# Mainboard.net
KiCad netlist of a schematic drawn in EAGLE
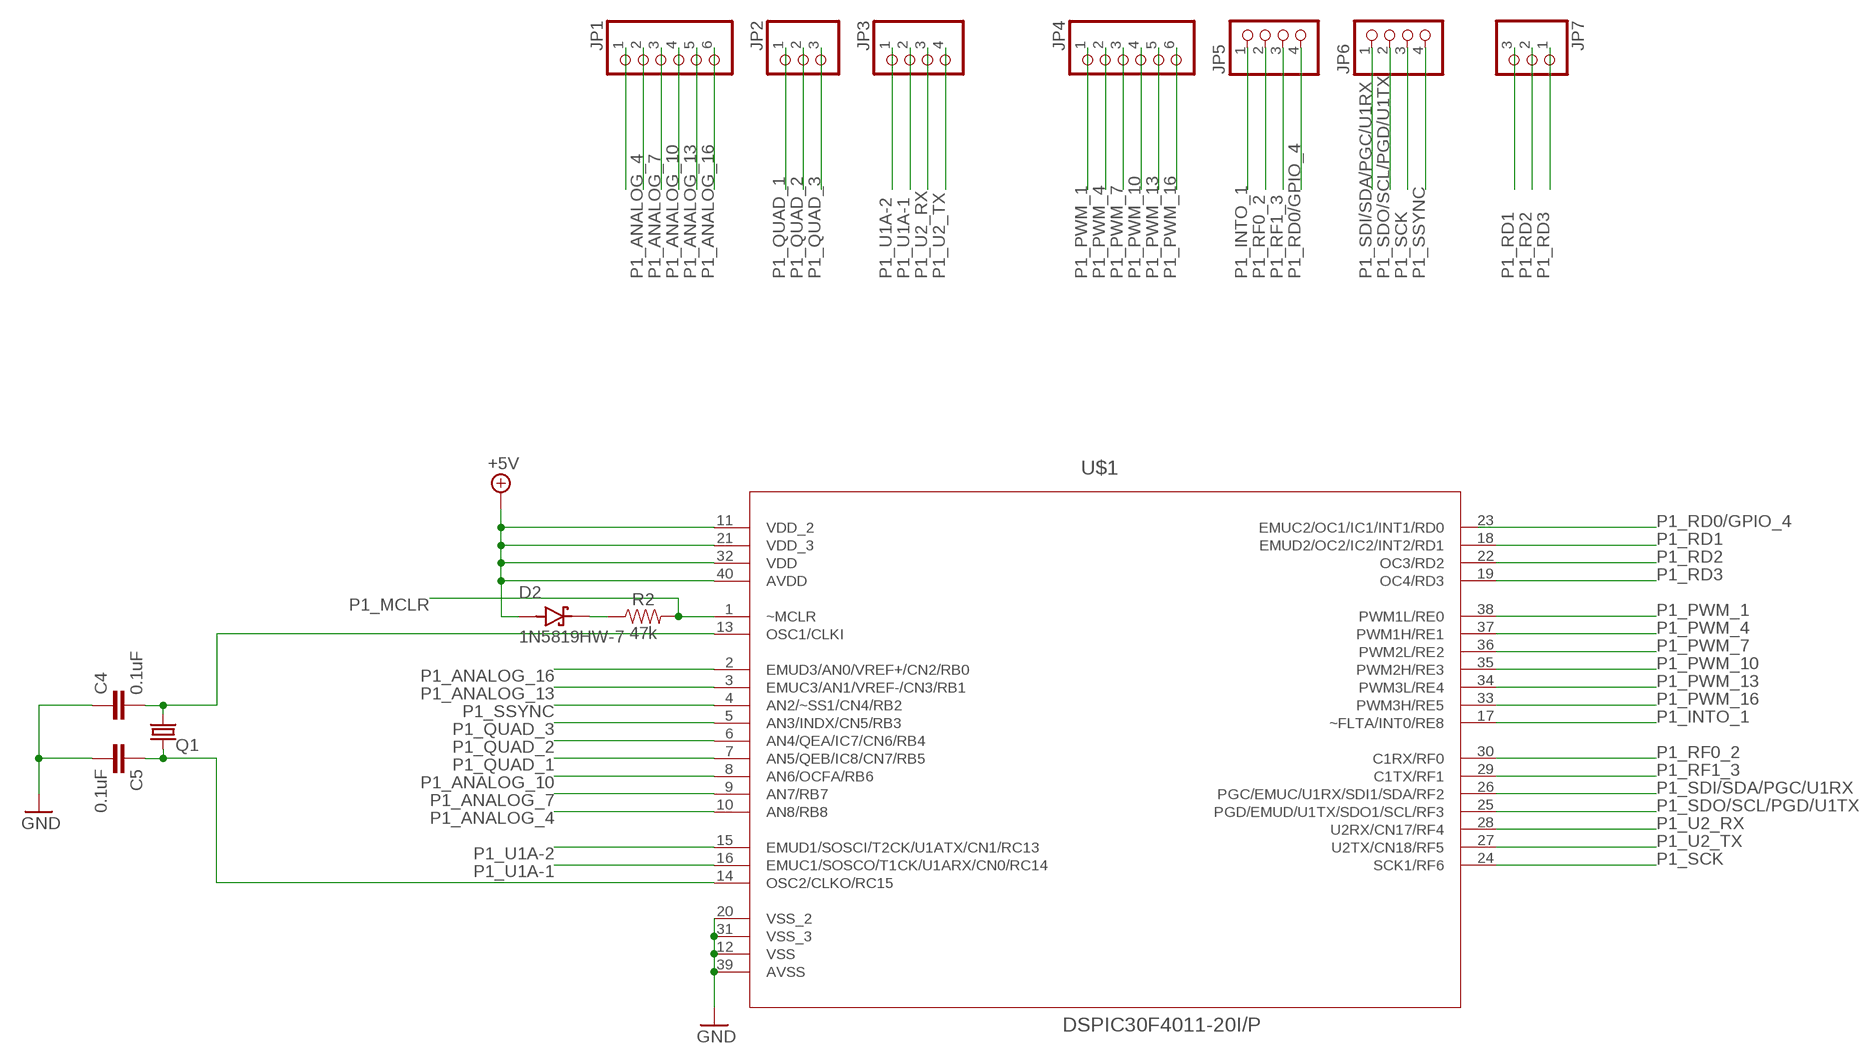
[diagram p0: schematic, sheet 2]
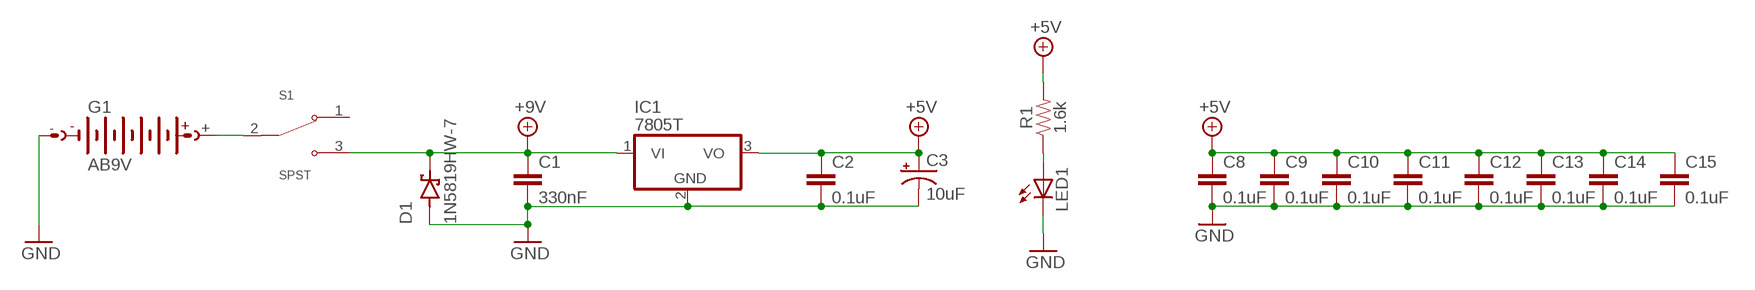
[diagram p1: schematic, sheet 3]
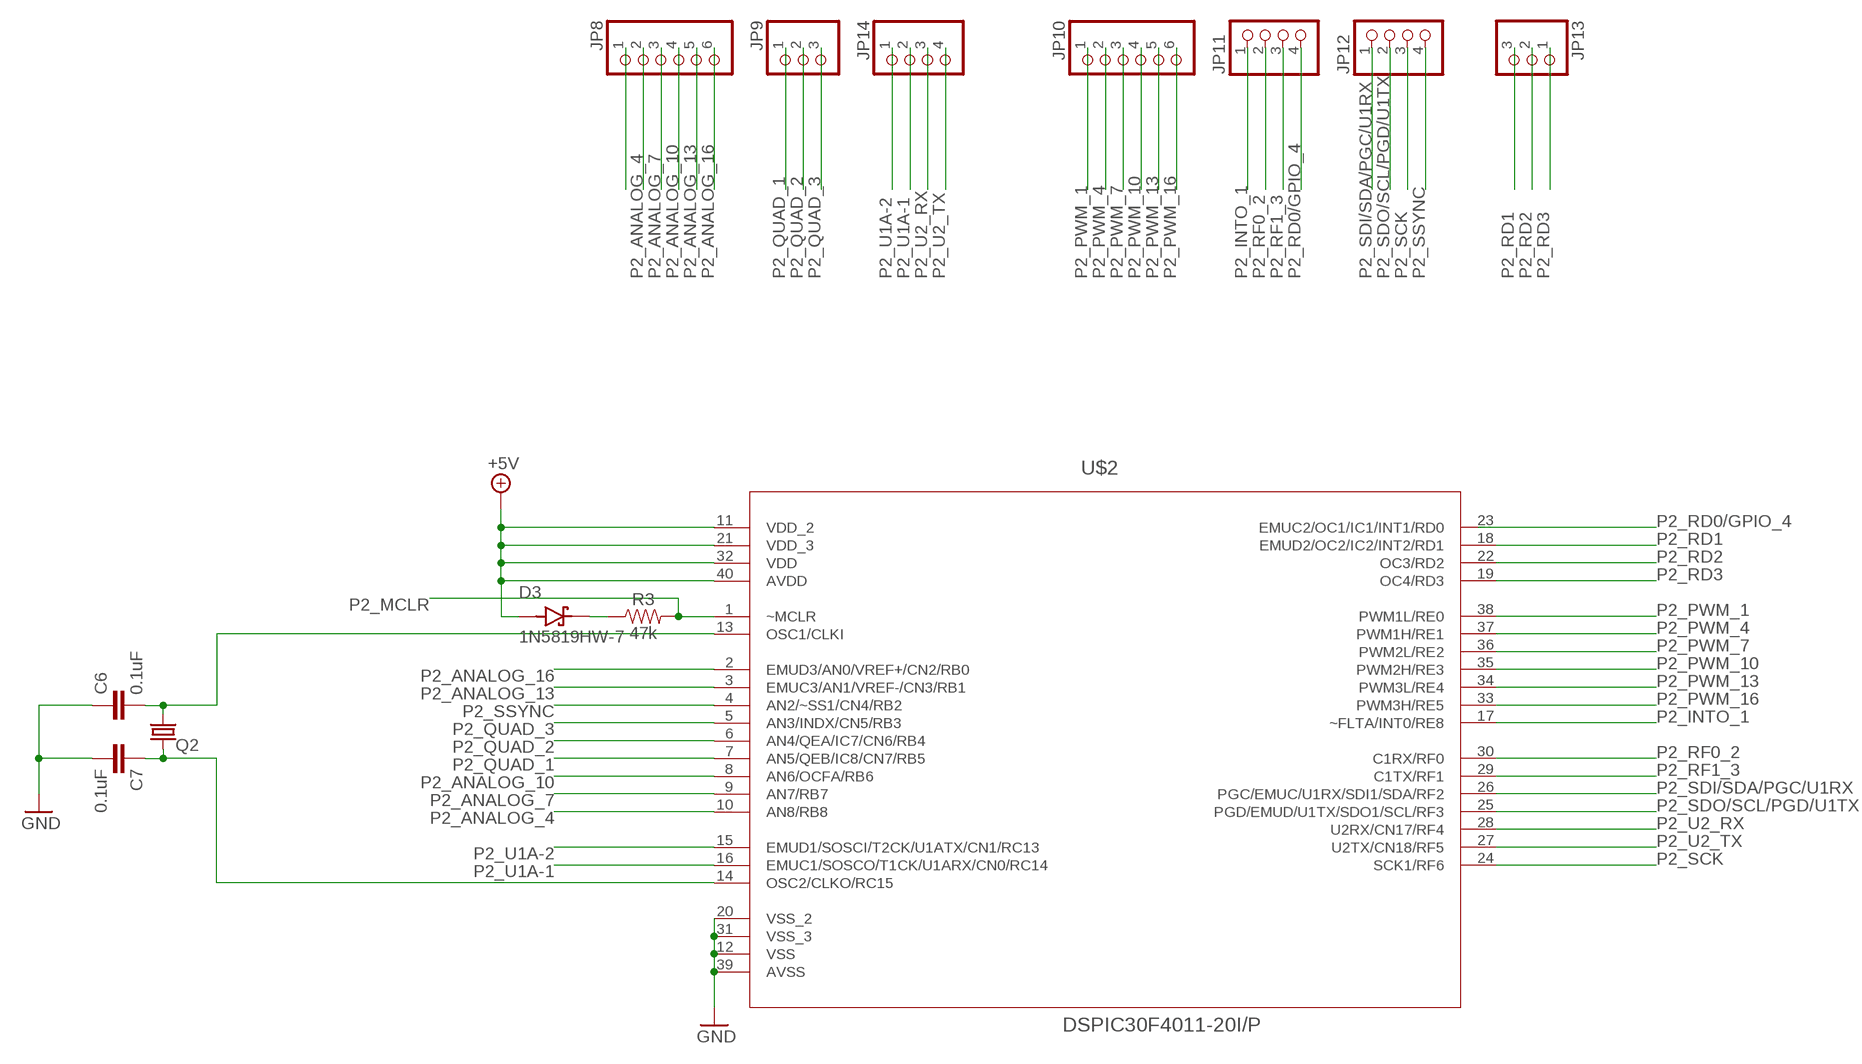
[diagram p2: schematic, sheet 4]
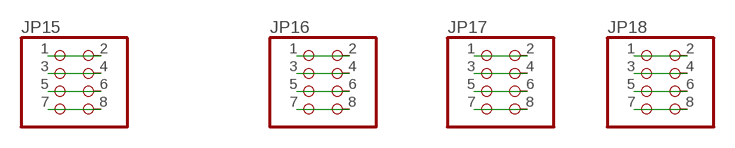
[diagram p3: schematic, sheet 5]

(export (version "E")
  (design (tool "Eeschema 10.0.6"))
  (components
    (comp (ref "JP15")
      (value "PINHD-2X4")
      (footprint "eagle-import:2X04")
      (libsource (lib "eagle-import") (part "PINHD-2X4"))
    )
    (comp (ref "JP16")
      (value "PINHD-2X4")
      (footprint "eagle-import:2X04")
      (libsource (lib "eagle-import") (part "PINHD-2X4"))
    )
    (comp (ref "JP17")
      (value "PINHD-2X4")
      (footprint "eagle-import:2X04")
      (libsource (lib "eagle-import") (part "PINHD-2X4"))
    )
    (comp (ref "JP18")
      (value "PINHD-2X4")
      (footprint "eagle-import:2X04")
      (libsource (lib "eagle-import") (part "PINHD-2X4"))
    )
    (comp (ref "C1")
      (value "330nF")
      (footprint "eagle-import:0603")
      (libsource (lib "eagle-import") (part "0.1UF-0603-25V-5%"))
    )
    (comp (ref "C2")
      (value "0.1uF")
      (footprint "eagle-import:0603")
      (libsource (lib "eagle-import") (part "0.1UF-0603-25V-5%"))
    )
    (comp (ref "C3")
      (value "10uF")
      (footprint "eagle-import:CPOL-RADIAL-2.5MM-5MM")
      (libsource (lib "eagle-import") (part "10UF-POLAR-RADIAL-2.5MM-25V-20%"))
    )
    (comp (ref "C8")
      (value "0.1uF")
      (footprint "eagle-import:0603")
      (libsource (lib "eagle-import") (part "0.1UF-0603-25V-5%"))
    )
    (comp (ref "C9")
      (value "0.1uF")
      (footprint "eagle-import:0603")
      (libsource (lib "eagle-import") (part "0.1UF-0603-25V-5%"))
    )
    (comp (ref "C10")
      (value "0.1uF")
      (footprint "eagle-import:0603")
      (libsource (lib "eagle-import") (part "0.1UF-0603-25V-5%"))
    )
    (comp (ref "C11")
      (value "0.1uF")
      (footprint "eagle-import:0603")
      (libsource (lib "eagle-import") (part "0.1UF-0603-25V-5%"))
    )
    (comp (ref "C12")
      (value "0.1uF")
      (footprint "eagle-import:0603")
      (libsource (lib "eagle-import") (part "0.1UF-0603-25V-5%"))
    )
    (comp (ref "C13")
      (value "0.1uF")
      (footprint "eagle-import:0603")
      (libsource (lib "eagle-import") (part "0.1UF-0603-25V-5%"))
    )
    (comp (ref "C14")
      (value "0.1uF")
      (footprint "eagle-import:0603")
      (libsource (lib "eagle-import") (part "0.1UF-0603-25V-5%"))
    )
    (comp (ref "C15")
      (value "0.1uF")
      (footprint "eagle-import:0603")
      (libsource (lib "eagle-import") (part "0.1UF-0603-25V-5%"))
    )
    (comp (ref "D1")
      (value "1N5819HW-7")
      (footprint "eagle-import:SOD3715X145N")
      (fields (field (name "MF") "Diodes Inc."))
      (libsource (lib "eagle-import") (part "1N5819HW-7"))
    )
    (comp (ref "G1")
      (value "AB9V")
      (footprint "eagle-import:AB9V")
      (libsource (lib "eagle-import") (part "AB9V"))
    )
    (comp (ref "IC1")
      (value "7805T")
      (footprint "eagle-import:TO220H")
      (libsource (lib "eagle-import") (part "78T05"))
    )
    (comp (ref "LED1")
      (value "LED3MM")
      (footprint "eagle-import:LED3MM")
      (libsource (lib "eagle-import") (part "LED3MM"))
    )
    (comp (ref "R1")
      (value "1.6k")
      (footprint "eagle-import:0603")
      (libsource (lib "eagle-import") (part "10KOHM-0603-1/10W-1%"))
    )
    (comp (ref "S1")
      (value "SPST")
      (footprint "eagle-import:SPST")
      (fields (field (name "MF") "E-Switch") (field (name "MP") "100SP1T1B4M2QE"))
      (libsource (lib "eagle-import") (part "SPST"))
    )
    (comp (ref "C6")
      (value "0.1uF")
      (footprint "eagle-import:0603")
      (libsource (lib "eagle-import") (part "SparkFun-Capacitors@1_0.1UF-0603-100V-10%"))
    )
    (comp (ref "C7")
      (value "0.1uF")
      (footprint "eagle-import:0603")
      (libsource (lib "eagle-import") (part "SparkFun-Capacitors@1_0.1UF-0603-100V-10%"))
    )
    (comp (ref "D3")
      (value "1N5819HW-7")
      (footprint "eagle-import:SOD3715X145N")
      (fields (field (name "MF") "Diodes Inc."))
      (libsource (lib "eagle-import") (part "1N5819HW-7"))
    )
    (comp (ref "JP8")
      (value "PINHD-1X6")
      (footprint "eagle-import:1X06")
      (libsource (lib "eagle-import") (part "PINHD-1X6"))
    )
    (comp (ref "JP9")
      (value "PINHD-1X3")
      (footprint "eagle-import:1X03")
      (libsource (lib "eagle-import") (part "PINHD-1X3"))
    )
    (comp (ref "JP10")
      (value "PINHD-1X6")
      (footprint "eagle-import:1X06")
      (libsource (lib "eagle-import") (part "PINHD-1X6"))
    )
    (comp (ref "JP11")
      (value "PINHD-1X4")
      (footprint "eagle-import:1X04")
      (libsource (lib "eagle-import") (part "pinhead@1_PINHD-1X4"))
    )
    (comp (ref "JP12")
      (value "PINHD-1X4")
      (footprint "eagle-import:1X04")
      (libsource (lib "eagle-import") (part "pinhead@1_PINHD-1X4"))
    )
    (comp (ref "JP13")
      (value "PINHD-1X3")
      (footprint "eagle-import:1X03")
      (libsource (lib "eagle-import") (part "PINHD-1X3"))
    )
    (comp (ref "JP14")
      (value "PINHD-1X4")
      (footprint "eagle-import:1X04")
      (libsource (lib "eagle-import") (part "pinhead@1_PINHD-1X4"))
    )
    (comp (ref "Q2")
      (value "CRYSTALHC49UP")
      (footprint "eagle-import:HC49UP")
      (libsource (lib "eagle-import") (part "CRYSTALHC49UP"))
    )
    (comp (ref "R3")
      (value "47k")
      (footprint "eagle-import:0603")
      (libsource (lib "eagle-import") (part "SparkFun-Resistors@1_10KOHM-0603-1/10W-1%"))
    )
    (comp (ref "U$2")
      (value "DSPIC30F4011-20I/P")
      (footprint "eagle-import:DIP254P1524X635-40")
      (libsource (lib "eagle-import") (part "DSPIC30F4011-20I/P"))
    )
    (comp (ref "C4")
      (value "0.1uF")
      (footprint "eagle-import:0603")
      (libsource (lib "eagle-import") (part "0.1UF-0603-100V-10%"))
    )
    (comp (ref "C5")
      (value "0.1uF")
      (footprint "eagle-import:0603")
      (libsource (lib "eagle-import") (part "0.1UF-0603-100V-10%"))
    )
    (comp (ref "D2")
      (value "1N5819HW-7")
      (footprint "eagle-import:SOD3715X145N")
      (fields (field (name "MF") "Diodes Inc."))
      (libsource (lib "eagle-import") (part "1N5819HW-7"))
    )
    (comp (ref "JP1")
      (value "PINHD-1X6")
      (footprint "eagle-import:1X06")
      (libsource (lib "eagle-import") (part "PINHD-1X6"))
    )
    (comp (ref "JP2")
      (value "PINHD-1X3")
      (footprint "eagle-import:1X03")
      (libsource (lib "eagle-import") (part "PINHD-1X3"))
    )
    (comp (ref "JP3")
      (value "PINHD-1X4")
      (footprint "eagle-import:1X04")
      (libsource (lib "eagle-import") (part "PINHD-1X4"))
    )
    (comp (ref "JP4")
      (value "PINHD-1X6")
      (footprint "eagle-import:1X06")
      (libsource (lib "eagle-import") (part "PINHD-1X6"))
    )
    (comp (ref "JP5")
      (value "PINHD-1X4")
      (footprint "eagle-import:1X04")
      (libsource (lib "eagle-import") (part "PINHD-1X4"))
    )
    (comp (ref "JP6")
      (value "PINHD-1X4")
      (footprint "eagle-import:1X04")
      (libsource (lib "eagle-import") (part "PINHD-1X4"))
    )
    (comp (ref "JP7")
      (value "PINHD-1X3")
      (footprint "eagle-import:1X03")
      (libsource (lib "eagle-import") (part "PINHD-1X3"))
    )
    (comp (ref "Q1")
      (value "CRYSTALHC49UP")
      (footprint "eagle-import:HC49UP")
      (libsource (lib "eagle-import") (part "CRYSTALHC49UP"))
    )
    (comp (ref "R2")
      (value "47k")
      (footprint "eagle-import:0603")
      (libsource (lib "eagle-import") (part "10KOHM-0603-1/10W-1%"))
    )
    (comp (ref "U$1")
      (value "DSPIC30F4011-20I/P")
      (footprint "eagle-import:DIP254P1524X635-40")
      (libsource (lib "eagle-import") (part "DSPIC30F4011-20I/P"))
    )
  )
  (nets
    (net (code "1") (name "+5V") (class "Default")
      (node (ref "C10") (pin "1") (pinfunction "1_1") (pintype "passive"))
      (node (ref "C11") (pin "1") (pinfunction "1_1") (pintype "passive"))
      (node (ref "C12") (pin "1") (pinfunction "1_1") (pintype "passive"))
      (node (ref "C13") (pin "1") (pinfunction "1_1") (pintype "passive"))
      (node (ref "C14") (pin "1") (pinfunction "1_1") (pintype "passive"))
      (node (ref "C15") (pin "1") (pinfunction "1_1") (pintype "passive"))
      (node (ref "C2") (pin "1") (pinfunction "1_1") (pintype "passive"))
      (node (ref "C3") (pin "1") (pinfunction "+_1") (pintype "passive"))
      (node (ref "C8") (pin "1") (pinfunction "1_1") (pintype "passive"))
      (node (ref "C9") (pin "1") (pinfunction "1_1") (pintype "passive"))
      (node (ref "D2") (pin "A") (pinfunction "A_A") (pintype "passive"))
      (node (ref "D3") (pin "A") (pinfunction "A_A") (pintype "passive"))
      (node (ref "IC1") (pin "3") (pinfunction "VO_3") (pintype "passive"))
      (node (ref "R1") (pin "2") (pinfunction "2_2") (pintype "passive"))
      (node (ref "U$1") (pin "11") (pinfunction "VDD_2_11") (pintype "power_in"))
      (node (ref "U$1") (pin "21") (pinfunction "VDD_3_21") (pintype "power_in"))
      (node (ref "U$1") (pin "32") (pinfunction "VDD_32") (pintype "power_in"))
      (node (ref "U$1") (pin "40") (pinfunction "AVDD_40") (pintype "power_in"))
      (node (ref "U$2") (pin "11") (pinfunction "VDD_2_11") (pintype "power_in"))
      (node (ref "U$2") (pin "21") (pinfunction "VDD_3_21") (pintype "power_in"))
      (node (ref "U$2") (pin "32") (pinfunction "VDD_32") (pintype "power_in"))
      (node (ref "U$2") (pin "40") (pinfunction "AVDD_40") (pintype "power_in"))
    )
    (net (code "2") (name "+9V") (class "Default")
      (node (ref "C1") (pin "1") (pinfunction "1_1") (pintype "passive"))
      (node (ref "D1") (pin "C") (pinfunction "K_C") (pintype "passive"))
      (node (ref "IC1") (pin "1") (pinfunction "VI_1") (pintype "input"))
      (node (ref "S1") (pin "3") (pinfunction "3_3") (pintype "passive"))
    )
    (net (code "3") (name "GND") (class "Default")
      (node (ref "C1") (pin "2") (pinfunction "2_2") (pintype "passive"))
      (node (ref "C10") (pin "2") (pinfunction "2_2") (pintype "passive"))
      (node (ref "C11") (pin "2") (pinfunction "2_2") (pintype "passive"))
      (node (ref "C12") (pin "2") (pinfunction "2_2") (pintype "passive"))
      (node (ref "C13") (pin "2") (pinfunction "2_2") (pintype "passive"))
      (node (ref "C14") (pin "2") (pinfunction "2_2") (pintype "passive"))
      (node (ref "C15") (pin "2") (pinfunction "2_2") (pintype "passive"))
      (node (ref "C2") (pin "2") (pinfunction "2_2") (pintype "passive"))
      (node (ref "C3") (pin "2") (pinfunction "-_2") (pintype "passive"))
      (node (ref "C4") (pin "1") (pinfunction "1_1") (pintype "passive"))
      (node (ref "C5") (pin "2") (pinfunction "2_2") (pintype "passive"))
      (node (ref "C6") (pin "1") (pinfunction "1_1") (pintype "passive"))
      (node (ref "C7") (pin "2") (pinfunction "2_2") (pintype "passive"))
      (node (ref "C8") (pin "2") (pinfunction "2_2") (pintype "passive"))
      (node (ref "C9") (pin "2") (pinfunction "2_2") (pintype "passive"))
      (node (ref "D1") (pin "A") (pinfunction "A_A") (pintype "passive"))
      (node (ref "G1") (pin "-") (pinfunction "-_-") (pintype "passive"))
      (node (ref "IC1") (pin "2") (pinfunction "GND_2") (pintype "passive"))
      (node (ref "LED1") (pin "K") (pinfunction "C_K") (pintype "passive"))
      (node (ref "U$1") (pin "12") (pinfunction "VSS_12") (pintype "power_in"))
      (node (ref "U$1") (pin "20") (pinfunction "VSS_2_20") (pintype "power_in"))
      (node (ref "U$1") (pin "31") (pinfunction "VSS_3_31") (pintype "power_in"))
      (node (ref "U$1") (pin "39") (pinfunction "AVSS_39") (pintype "power_in"))
      (node (ref "U$2") (pin "12") (pinfunction "VSS_12") (pintype "power_in"))
      (node (ref "U$2") (pin "20") (pinfunction "VSS_2_20") (pintype "power_in"))
      (node (ref "U$2") (pin "31") (pinfunction "VSS_3_31") (pintype "power_in"))
      (node (ref "U$2") (pin "39") (pinfunction "AVSS_39") (pintype "power_in"))
    )
    (net (code "4") (name "Net-(D2-K)") (class "Default")
      (node (ref "D2") (pin "C") (pinfunction "K_C") (pintype "passive"))
      (node (ref "R2") (pin "1") (pinfunction "1_1") (pintype "passive"))
    )
    (net (code "5") (name "Net-(D3-K)") (class "Default")
      (node (ref "D3") (pin "C") (pinfunction "K_C") (pintype "passive"))
      (node (ref "R3") (pin "1") (pinfunction "1_1") (pintype "passive"))
    )
    (net (code "6") (name "Net-(G1-Pad+)") (class "Default")
      (node (ref "G1") (pin "+") (pinfunction "+_+") (pintype "passive"))
      (node (ref "S1") (pin "2") (pinfunction "2_2") (pintype "passive"))
    )
    (net (code "7") (name "Net-(JP15-Pad1)") (class "Default")
      (node (ref "JP15") (pin "1") (pinfunction "1_1") (pintype "passive"))
      (node (ref "JP15") (pin "2") (pinfunction "2_2") (pintype "passive"))
    )
    (net (code "8") (name "Net-(JP15-Pad3)") (class "Default")
      (node (ref "JP15") (pin "3") (pinfunction "3_3") (pintype "passive"))
      (node (ref "JP15") (pin "4") (pinfunction "4_4") (pintype "passive"))
    )
    (net (code "9") (name "Net-(JP15-Pad5)") (class "Default")
      (node (ref "JP15") (pin "5") (pinfunction "5_5") (pintype "passive"))
      (node (ref "JP15") (pin "6") (pinfunction "6_6") (pintype "passive"))
    )
    (net (code "10") (name "Net-(JP15-Pad7)") (class "Default")
      (node (ref "JP15") (pin "7") (pinfunction "7_7") (pintype "passive"))
      (node (ref "JP15") (pin "8") (pinfunction "8_8") (pintype "passive"))
    )
    (net (code "11") (name "Net-(JP16-Pad1)") (class "Default")
      (node (ref "JP16") (pin "1") (pinfunction "1_1") (pintype "passive"))
      (node (ref "JP16") (pin "2") (pinfunction "2_2") (pintype "passive"))
    )
    (net (code "12") (name "Net-(JP16-Pad3)") (class "Default")
      (node (ref "JP16") (pin "3") (pinfunction "3_3") (pintype "passive"))
      (node (ref "JP16") (pin "4") (pinfunction "4_4") (pintype "passive"))
    )
    (net (code "13") (name "Net-(JP16-Pad5)") (class "Default")
      (node (ref "JP16") (pin "5") (pinfunction "5_5") (pintype "passive"))
      (node (ref "JP16") (pin "6") (pinfunction "6_6") (pintype "passive"))
    )
    (net (code "14") (name "Net-(JP16-Pad7)") (class "Default")
      (node (ref "JP16") (pin "7") (pinfunction "7_7") (pintype "passive"))
      (node (ref "JP16") (pin "8") (pinfunction "8_8") (pintype "passive"))
    )
    (net (code "15") (name "Net-(JP17-Pad1)") (class "Default")
      (node (ref "JP17") (pin "1") (pinfunction "1_1") (pintype "passive"))
      (node (ref "JP17") (pin "2") (pinfunction "2_2") (pintype "passive"))
    )
    (net (code "16") (name "Net-(JP17-Pad3)") (class "Default")
      (node (ref "JP17") (pin "3") (pinfunction "3_3") (pintype "passive"))
      (node (ref "JP17") (pin "4") (pinfunction "4_4") (pintype "passive"))
    )
    (net (code "17") (name "Net-(JP17-Pad5)") (class "Default")
      (node (ref "JP17") (pin "5") (pinfunction "5_5") (pintype "passive"))
      (node (ref "JP17") (pin "6") (pinfunction "6_6") (pintype "passive"))
    )
    (net (code "18") (name "Net-(JP17-Pad7)") (class "Default")
      (node (ref "JP17") (pin "7") (pinfunction "7_7") (pintype "passive"))
      (node (ref "JP17") (pin "8") (pinfunction "8_8") (pintype "passive"))
    )
    (net (code "19") (name "Net-(JP18-Pad1)") (class "Default")
      (node (ref "JP18") (pin "1") (pinfunction "1_1") (pintype "passive"))
      (node (ref "JP18") (pin "2") (pinfunction "2_2") (pintype "passive"))
    )
    (net (code "20") (name "Net-(JP18-Pad3)") (class "Default")
      (node (ref "JP18") (pin "3") (pinfunction "3_3") (pintype "passive"))
      (node (ref "JP18") (pin "4") (pinfunction "4_4") (pintype "passive"))
    )
    (net (code "21") (name "Net-(JP18-Pad5)") (class "Default")
      (node (ref "JP18") (pin "5") (pinfunction "5_5") (pintype "passive"))
      (node (ref "JP18") (pin "6") (pinfunction "6_6") (pintype "passive"))
    )
    (net (code "22") (name "Net-(JP18-Pad7)") (class "Default")
      (node (ref "JP18") (pin "7") (pinfunction "7_7") (pintype "passive"))
      (node (ref "JP18") (pin "8") (pinfunction "8_8") (pintype "passive"))
    )
    (net (code "23") (name "Net-(LED1-PadA)") (class "Default")
      (node (ref "LED1") (pin "A") (pinfunction "A_A") (pintype "passive"))
      (node (ref "R1") (pin "1") (pinfunction "1_1") (pintype "passive"))
    )
    (net (code "24") (name "Net-(U$1-OSC1{slash}CLKI)") (class "Default")
      (node (ref "C4") (pin "2") (pinfunction "2_2") (pintype "passive"))
      (node (ref "Q1") (pin "2") (pinfunction "2_2") (pintype "passive"))
      (node (ref "U$1") (pin "13") (pinfunction "OSC1/CLKI_13") (pintype "input"))
    )
    (net (code "25") (name "Net-(U$1-OSC2{slash}CLKO{slash}RC15)") (class "Default")
      (node (ref "C5") (pin "1") (pinfunction "1_1") (pintype "passive"))
      (node (ref "Q1") (pin "1") (pinfunction "1_1") (pintype "passive"))
      (node (ref "U$1") (pin "14") (pinfunction "OSC2/CLKO/RC15_14") (pintype "bidirectional"))
    )
    (net (code "26") (name "Net-(U$2-OSC1{slash}CLKI)") (class "Default")
      (node (ref "C6") (pin "2") (pinfunction "2_2") (pintype "passive"))
      (node (ref "Q2") (pin "2") (pinfunction "2_2") (pintype "passive"))
      (node (ref "U$2") (pin "13") (pinfunction "OSC1/CLKI_13") (pintype "input"))
    )
    (net (code "27") (name "Net-(U$2-OSC2{slash}CLKO{slash}RC15)") (class "Default")
      (node (ref "C7") (pin "1") (pinfunction "1_1") (pintype "passive"))
      (node (ref "Q2") (pin "1") (pinfunction "1_1") (pintype "passive"))
      (node (ref "U$2") (pin "14") (pinfunction "OSC2/CLKO/RC15_14") (pintype "bidirectional"))
    )
    (net (code "28") (name "P1_ANALOG_4") (class "Default")
      (node (ref "JP1") (pin "2") (pinfunction "2_2") (pintype "passive"))
      (node (ref "U$1") (pin "10") (pinfunction "AN8/RB8_10") (pintype "bidirectional"))
    )
    (net (code "29") (name "P1_ANALOG_7") (class "Default")
      (node (ref "JP1") (pin "3") (pinfunction "3_3") (pintype "passive"))
      (node (ref "U$1") (pin "9") (pinfunction "AN7/RB7_9") (pintype "bidirectional"))
    )
    (net (code "30") (name "P1_ANALOG_10") (class "Default")
      (node (ref "JP1") (pin "4") (pinfunction "4_4") (pintype "passive"))
      (node (ref "U$1") (pin "8") (pinfunction "AN6/OCFA/RB6_8") (pintype "bidirectional"))
    )
    (net (code "31") (name "P1_ANALOG_13") (class "Default")
      (node (ref "JP1") (pin "5") (pinfunction "5_5") (pintype "passive"))
      (node (ref "U$1") (pin "3") (pinfunction "EMUC3/AN1/VREF-/CN3/RB1_3") (pintype "bidirectional"))
    )
    (net (code "32") (name "P1_ANALOG_16") (class "Default")
      (node (ref "JP1") (pin "6") (pinfunction "6_6") (pintype "passive"))
      (node (ref "U$1") (pin "2") (pinfunction "EMUD3/AN0/VREF+/CN2/RB0_2") (pintype "bidirectional"))
    )
    (net (code "33") (name "P1_INTO_1") (class "Default")
      (node (ref "JP5") (pin "1") (pinfunction "1_1") (pintype "passive"))
      (node (ref "U$1") (pin "17") (pinfunction "~{FLTA/INT0/RE8}_17") (pintype "bidirectional"))
    )
    (net (code "34") (name "P1_MCLR") (class "Default")
      (node (ref "R2") (pin "2") (pinfunction "2_2") (pintype "passive"))
      (node (ref "U$1") (pin "1") (pinfunction "~{MCLR}_1") (pintype "input"))
    )
    (net (code "35") (name "P1_PWM_1") (class "Default")
      (node (ref "JP4") (pin "1") (pinfunction "1_1") (pintype "passive"))
      (node (ref "U$1") (pin "38") (pinfunction "PWM1L/RE0_38") (pintype "bidirectional"))
    )
    (net (code "36") (name "P1_PWM_4") (class "Default")
      (node (ref "JP4") (pin "2") (pinfunction "2_2") (pintype "passive"))
      (node (ref "U$1") (pin "37") (pinfunction "PWM1H/RE1_37") (pintype "bidirectional"))
    )
    (net (code "37") (name "P1_PWM_7") (class "Default")
      (node (ref "JP4") (pin "3") (pinfunction "3_3") (pintype "passive"))
      (node (ref "U$1") (pin "36") (pinfunction "PWM2L/RE2_36") (pintype "bidirectional"))
    )
    (net (code "38") (name "P1_PWM_10") (class "Default")
      (node (ref "JP4") (pin "4") (pinfunction "4_4") (pintype "passive"))
      (node (ref "U$1") (pin "35") (pinfunction "PWM2H/RE3_35") (pintype "bidirectional"))
    )
    (net (code "39") (name "P1_PWM_13") (class "Default")
      (node (ref "JP4") (pin "5") (pinfunction "5_5") (pintype "passive"))
      (node (ref "U$1") (pin "34") (pinfunction "PWM3L/RE4_34") (pintype "bidirectional"))
    )
    (net (code "40") (name "P1_PWM_16") (class "Default")
      (node (ref "JP4") (pin "6") (pinfunction "6_6") (pintype "passive"))
      (node (ref "U$1") (pin "33") (pinfunction "PWM3H/RE5_33") (pintype "bidirectional"))
    )
    (net (code "41") (name "P1_QUAD_1") (class "Default")
      (node (ref "JP2") (pin "1") (pinfunction "1_1") (pintype "passive"))
      (node (ref "U$1") (pin "7") (pinfunction "AN5/QEB/IC8/CN7/RB5_7") (pintype "bidirectional"))
    )
    (net (code "42") (name "P1_QUAD_2") (class "Default")
      (node (ref "JP2") (pin "2") (pinfunction "2_2") (pintype "passive"))
      (node (ref "U$1") (pin "6") (pinfunction "AN4/QEA/IC7/CN6/RB4_6") (pintype "bidirectional"))
    )
    (net (code "43") (name "P1_QUAD_3") (class "Default")
      (node (ref "JP2") (pin "3") (pinfunction "3_3") (pintype "passive"))
      (node (ref "U$1") (pin "5") (pinfunction "AN3/INDX/CN5/RB3_5") (pintype "bidirectional"))
    )
    (net (code "44") (name "P1_RD0{slash}GPIO_4") (class "Default")
      (node (ref "JP5") (pin "4") (pinfunction "4_4") (pintype "passive"))
      (node (ref "U$1") (pin "23") (pinfunction "EMUC2/OC1/IC1/INT1/RD0_23") (pintype "bidirectional"))
    )
    (net (code "45") (name "P1_RD1") (class "Default")
      (node (ref "JP7") (pin "3") (pinfunction "3_3") (pintype "passive"))
      (node (ref "U$1") (pin "18") (pinfunction "EMUD2/OC2/IC2/INT2/RD1_18") (pintype "bidirectional"))
    )
    (net (code "46") (name "P1_RD2") (class "Default")
      (node (ref "JP7") (pin "2") (pinfunction "2_2") (pintype "passive"))
      (node (ref "U$1") (pin "22") (pinfunction "OC3/RD2_22") (pintype "bidirectional"))
    )
    (net (code "47") (name "P1_RD3") (class "Default")
      (node (ref "JP7") (pin "1") (pinfunction "1_1") (pintype "passive"))
      (node (ref "U$1") (pin "19") (pinfunction "OC4/RD3_19") (pintype "bidirectional"))
    )
    (net (code "48") (name "P1_RF0_2") (class "Default")
      (node (ref "JP5") (pin "2") (pinfunction "2_2") (pintype "passive"))
      (node (ref "U$1") (pin "30") (pinfunction "C1RX/RF0_30") (pintype "bidirectional"))
    )
    (net (code "49") (name "P1_RF1_3") (class "Default")
      (node (ref "JP5") (pin "3") (pinfunction "3_3") (pintype "passive"))
      (node (ref "U$1") (pin "29") (pinfunction "C1TX/RF1_29") (pintype "bidirectional"))
    )
    (net (code "50") (name "P1_SCK") (class "Default")
      (node (ref "JP6") (pin "3") (pinfunction "3_3") (pintype "passive"))
      (node (ref "U$1") (pin "24") (pinfunction "SCK1/RF6_24") (pintype "bidirectional"))
    )
    (net (code "51") (name "P1_SDI{slash}SDA{slash}PGC{slash}U1RX") (class "Default")
      (node (ref "JP6") (pin "1") (pinfunction "1_1") (pintype "passive"))
      (node (ref "U$1") (pin "26") (pinfunction "PGC/EMUC/U1RX/SDI1/SDA/RF2_26") (pintype "bidirectional"))
    )
    (net (code "52") (name "P1_SDO{slash}SCL{slash}PGD{slash}U1TX") (class "Default")
      (node (ref "JP6") (pin "2") (pinfunction "2_2") (pintype "passive"))
      (node (ref "U$1") (pin "25") (pinfunction "PGD/EMUD/U1TX/SDO1/SCL/RF3_25") (pintype "bidirectional"))
    )
    (net (code "53") (name "P1_SSYNC") (class "Default")
      (node (ref "JP6") (pin "4") (pinfunction "4_4") (pintype "passive"))
      (node (ref "U$1") (pin "4") (pinfunction "AN2/~{SS1/CN4/RB2}_4") (pintype "bidirectional"))
    )
    (net (code "54") (name "P1_U1A-1") (class "Default")
      (node (ref "JP3") (pin "2") (pinfunction "2_2") (pintype "passive"))
      (node (ref "U$1") (pin "16") (pinfunction "EMUC1/SOSCO/T1CK/U1ARX/CN0/RC14_16") (pintype "bidirectional"))
    )
    (net (code "55") (name "P1_U1A-2") (class "Default")
      (node (ref "JP3") (pin "1") (pinfunction "1_1") (pintype "passive"))
      (node (ref "U$1") (pin "15") (pinfunction "EMUD1/SOSCI/T2CK/U1ATX/CN1/RC13_15") (pintype "bidirectional"))
    )
    (net (code "56") (name "P1_U2_RX") (class "Default")
      (node (ref "JP3") (pin "3") (pinfunction "3_3") (pintype "passive"))
      (node (ref "U$1") (pin "28") (pinfunction "U2RX/CN17/RF4_28") (pintype "bidirectional"))
    )
    (net (code "57") (name "P1_U2_TX") (class "Default")
      (node (ref "JP3") (pin "4") (pinfunction "4_4") (pintype "passive"))
      (node (ref "U$1") (pin "27") (pinfunction "U2TX/CN18/RF5_27") (pintype "bidirectional"))
    )
    (net (code "58") (name "P2_ANALOG_4") (class "Default")
      (node (ref "JP8") (pin "2") (pinfunction "2_2") (pintype "passive"))
      (node (ref "U$2") (pin "10") (pinfunction "AN8/RB8_10") (pintype "bidirectional"))
    )
    (net (code "59") (name "P2_ANALOG_7") (class "Default")
      (node (ref "JP8") (pin "3") (pinfunction "3_3") (pintype "passive"))
      (node (ref "U$2") (pin "9") (pinfunction "AN7/RB7_9") (pintype "bidirectional"))
    )
    (net (code "60") (name "P2_ANALOG_10") (class "Default")
      (node (ref "JP8") (pin "4") (pinfunction "4_4") (pintype "passive"))
      (node (ref "U$2") (pin "8") (pinfunction "AN6/OCFA/RB6_8") (pintype "bidirectional"))
    )
    (net (code "61") (name "P2_ANALOG_13") (class "Default")
      (node (ref "JP8") (pin "5") (pinfunction "5_5") (pintype "passive"))
      (node (ref "U$2") (pin "3") (pinfunction "EMUC3/AN1/VREF-/CN3/RB1_3") (pintype "bidirectional"))
    )
    (net (code "62") (name "P2_ANALOG_16") (class "Default")
      (node (ref "JP8") (pin "6") (pinfunction "6_6") (pintype "passive"))
      (node (ref "U$2") (pin "2") (pinfunction "EMUD3/AN0/VREF+/CN2/RB0_2") (pintype "bidirectional"))
    )
    (net (code "63") (name "P2_INTO_1") (class "Default")
      (node (ref "JP11") (pin "1") (pinfunction "1_1") (pintype "passive"))
      (node (ref "U$2") (pin "17") (pinfunction "~{FLTA/INT0/RE8}_17") (pintype "bidirectional"))
    )
    (net (code "64") (name "P2_MCLR") (class "Default")
      (node (ref "R3") (pin "2") (pinfunction "2_2") (pintype "passive"))
      (node (ref "U$2") (pin "1") (pinfunction "~{MCLR}_1") (pintype "input"))
    )
    (net (code "65") (name "P2_PWM_1") (class "Default")
      (node (ref "JP10") (pin "1") (pinfunction "1_1") (pintype "passive"))
      (node (ref "U$2") (pin "38") (pinfunction "PWM1L/RE0_38") (pintype "bidirectional"))
    )
    (net (code "66") (name "P2_PWM_4") (class "Default")
      (node (ref "JP10") (pin "2") (pinfunction "2_2") (pintype "passive"))
      (node (ref "U$2") (pin "37") (pinfunction "PWM1H/RE1_37") (pintype "bidirectional"))
    )
    (net (code "67") (name "P2_PWM_7") (class "Default")
      (node (ref "JP10") (pin "3") (pinfunction "3_3") (pintype "passive"))
      (node (ref "U$2") (pin "36") (pinfunction "PWM2L/RE2_36") (pintype "bidirectional"))
    )
    (net (code "68") (name "P2_PWM_10") (class "Default")
      (node (ref "JP10") (pin "4") (pinfunction "4_4") (pintype "passive"))
      (node (ref "U$2") (pin "35") (pinfunction "PWM2H/RE3_35") (pintype "bidirectional"))
    )
    (net (code "69") (name "P2_PWM_13") (class "Default")
      (node (ref "JP10") (pin "5") (pinfunction "5_5") (pintype "passive"))
      (node (ref "U$2") (pin "34") (pinfunction "PWM3L/RE4_34") (pintype "bidirectional"))
    )
    (net (code "70") (name "P2_PWM_16") (class "Default")
      (node (ref "JP10") (pin "6") (pinfunction "6_6") (pintype "passive"))
      (node (ref "U$2") (pin "33") (pinfunction "PWM3H/RE5_33") (pintype "bidirectional"))
    )
    (net (code "71") (name "P2_QUAD_1") (class "Default")
      (node (ref "JP9") (pin "1") (pinfunction "1_1") (pintype "passive"))
      (node (ref "U$2") (pin "7") (pinfunction "AN5/QEB/IC8/CN7/RB5_7") (pintype "bidirectional"))
    )
    (net (code "72") (name "P2_QUAD_2") (class "Default")
      (node (ref "JP9") (pin "2") (pinfunction "2_2") (pintype "passive"))
      (node (ref "U$2") (pin "6") (pinfunction "AN4/QEA/IC7/CN6/RB4_6") (pintype "bidirectional"))
    )
    (net (code "73") (name "P2_QUAD_3") (class "Default")
      (node (ref "JP9") (pin "3") (pinfunction "3_3") (pintype "passive"))
      (node (ref "U$2") (pin "5") (pinfunction "AN3/INDX/CN5/RB3_5") (pintype "bidirectional"))
    )
    (net (code "74") (name "P2_RD0{slash}GPIO_4") (class "Default")
      (node (ref "JP11") (pin "4") (pinfunction "4_4") (pintype "passive"))
      (node (ref "U$2") (pin "23") (pinfunction "EMUC2/OC1/IC1/INT1/RD0_23") (pintype "bidirectional"))
    )
    (net (code "75") (name "P2_RD1") (class "Default")
      (node (ref "JP13") (pin "3") (pinfunction "3_3") (pintype "passive"))
      (node (ref "U$2") (pin "18") (pinfunction "EMUD2/OC2/IC2/INT2/RD1_18") (pintype "bidirectional"))
    )
    (net (code "76") (name "P2_RD2") (class "Default")
      (node (ref "JP13") (pin "2") (pinfunction "2_2") (pintype "passive"))
      (node (ref "U$2") (pin "22") (pinfunction "OC3/RD2_22") (pintype "bidirectional"))
    )
    (net (code "77") (name "P2_RD3") (class "Default")
      (node (ref "JP13") (pin "1") (pinfunction "1_1") (pintype "passive"))
      (node (ref "U$2") (pin "19") (pinfunction "OC4/RD3_19") (pintype "bidirectional"))
    )
    (net (code "78") (name "P2_RF0_2") (class "Default")
      (node (ref "JP11") (pin "2") (pinfunction "2_2") (pintype "passive"))
      (node (ref "U$2") (pin "30") (pinfunction "C1RX/RF0_30") (pintype "bidirectional"))
    )
    (net (code "79") (name "P2_RF1_3") (class "Default")
      (node (ref "JP11") (pin "3") (pinfunction "3_3") (pintype "passive"))
      (node (ref "U$2") (pin "29") (pinfunction "C1TX/RF1_29") (pintype "bidirectional"))
    )
    (net (code "80") (name "P2_SCK") (class "Default")
      (node (ref "JP12") (pin "3") (pinfunction "3_3") (pintype "passive"))
      (node (ref "U$2") (pin "24") (pinfunction "SCK1/RF6_24") (pintype "bidirectional"))
    )
    (net (code "81") (name "P2_SDI{slash}SDA{slash}PGC{slash}U1RX") (class "Default")
      (node (ref "JP12") (pin "1") (pinfunction "1_1") (pintype "passive"))
      (node (ref "U$2") (pin "26") (pinfunction "PGC/EMUC/U1RX/SDI1/SDA/RF2_26") (pintype "bidirectional"))
    )
    (net (code "82") (name "P2_SDO{slash}SCL{slash}PGD{slash}U1TX") (class "Default")
      (node (ref "JP12") (pin "2") (pinfunction "2_2") (pintype "passive"))
      (node (ref "U$2") (pin "25") (pinfunction "PGD/EMUD/U1TX/SDO1/SCL/RF3_25") (pintype "bidirectional"))
    )
    (net (code "83") (name "P2_SSYNC") (class "Default")
      (node (ref "JP12") (pin "4") (pinfunction "4_4") (pintype "passive"))
      (node (ref "U$2") (pin "4") (pinfunction "AN2/~{SS1/CN4/RB2}_4") (pintype "bidirectional"))
    )
    (net (code "84") (name "P2_U1A-1") (class "Default")
      (node (ref "JP14") (pin "2") (pinfunction "2_2") (pintype "passive"))
      (node (ref "U$2") (pin "16") (pinfunction "EMUC1/SOSCO/T1CK/U1ARX/CN0/RC14_16") (pintype "bidirectional"))
    )
    (net (code "85") (name "P2_U1A-2") (class "Default")
      (node (ref "JP14") (pin "1") (pinfunction "1_1") (pintype "passive"))
      (node (ref "U$2") (pin "15") (pinfunction "EMUD1/SOSCI/T2CK/U1ATX/CN1/RC13_15") (pintype "bidirectional"))
    )
    (net (code "86") (name "P2_U2_RX") (class "Default")
      (node (ref "JP14") (pin "3") (pinfunction "3_3") (pintype "passive"))
      (node (ref "U$2") (pin "28") (pinfunction "U2RX/CN17/RF4_28") (pintype "bidirectional"))
    )
    (net (code "87") (name "P2_U2_TX") (class "Default")
      (node (ref "JP14") (pin "4") (pinfunction "4_4") (pintype "passive"))
      (node (ref "U$2") (pin "27") (pinfunction "U2TX/CN18/RF5_27") (pintype "bidirectional"))
    )
    (net (code "88") (name "unconnected-(JP1-Pad1)") (class "Default")
      (node (ref "JP1") (pin "1") (pinfunction "1_1") (pintype "passive"))
    )
    (net (code "89") (name "unconnected-(JP8-Pad1)") (class "Default")
      (node (ref "JP8") (pin "1") (pinfunction "1_1") (pintype "passive"))
    )
    (net (code "90") (name "unconnected-(S1-Pad1)") (class "Default")
      (node (ref "S1") (pin "1") (pinfunction "1_1") (pintype "passive"))
    )
  )
)
